# fpga-bank4-outside.net
KiCad netlist of a schematic drawn in Altium Designer
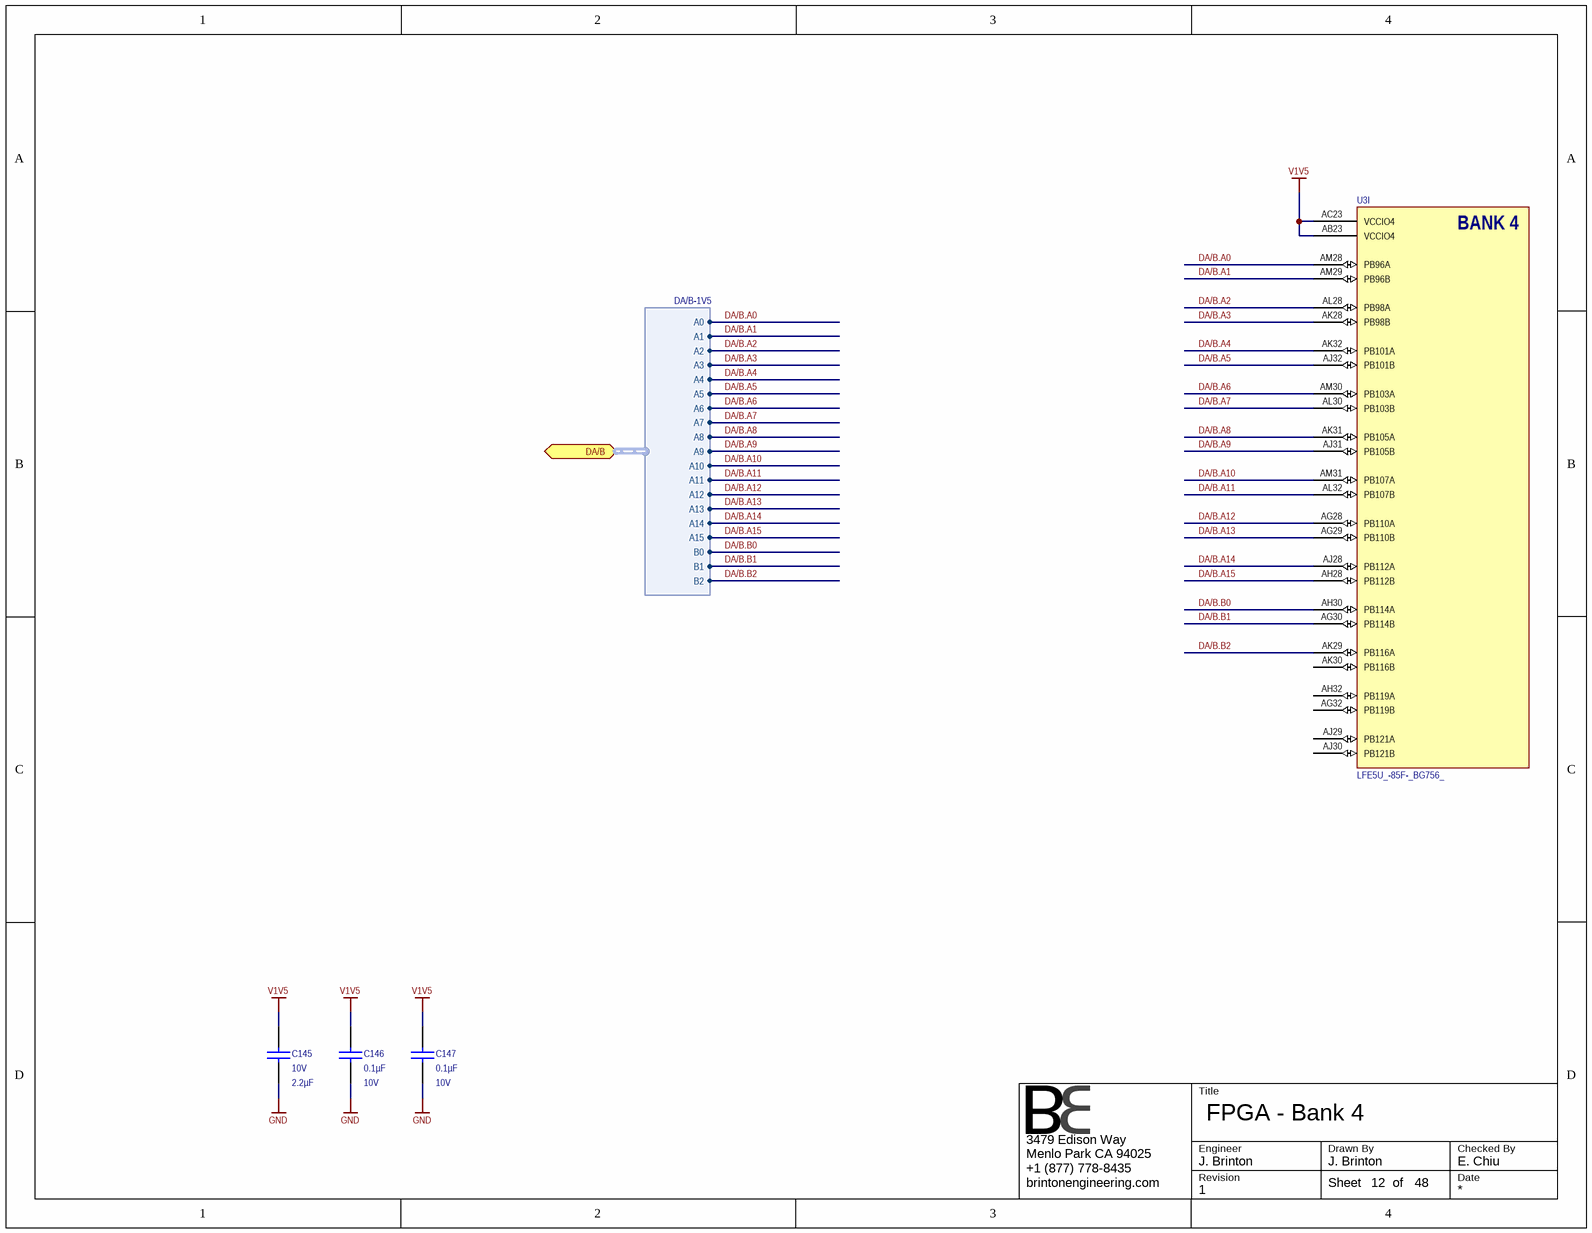
[diagram p0: fpga-bank4-outside.SchDoc]

(export (version "E")
  (design (tool "Eeschema 10.0.6"))
  (components
    (comp (ref "C145")
      (value "GRM188R71A225KE15D")
      (footprint "CAPC1608X90N")
      (description "CAP CER 2.2UF 10V 10% X7R 0603")
      (fields
        (field (name "MANUFACTURER") "Murata Electronics North America")
        (field (name "TOLERANCE") "±10%")
        (field (name "VOLTAGE - RATED") "10V")
        (field (name "CAPACITANCE") "2.2µF")
      )
      (libsource (lib "murata") (part "GRM188R71A225KE15D"))
    )
    (comp (ref "C146")
      (value "GRM155R71A104KA01J")
      (footprint "CAPC1005X56N")
      (description "CAP CER 0.1UF 10V 10% X7R 0402")
      (fields
        (field (name "MANUFACTURER") "Murata Electronics North America")
        (field (name "TOLERANCE") "±10%")
        (field (name "CAPACITANCE") "0.1µF")
        (field (name "VOLTAGE - RATED") "10V")
      )
      (libsource (lib "murata") (part "GRM155R71A104KA01J"))
    )
    (comp (ref "C147")
      (value "GRM155R71A104KA01J")
      (footprint "CAPC1005X56N")
      (description "CAP CER 0.1UF 10V 10% X7R 0402")
      (fields
        (field (name "MANUFACTURER") "Murata Electronics North America")
        (field (name "TOLERANCE") "±10%")
        (field (name "CAPACITANCE") "0.1µF")
        (field (name "VOLTAGE - RATED") "10V")
      )
      (libsource (lib "murata") (part "GRM155R71A104KA01J"))
    )
    (comp (ref "U3")
      (value "LFE5U_-85F-_BG756_")
      (footprint "lattice:caBGA756")
      (description "ECP5 FPGA, 85k LUT, 756-caBGA")
      (fields (field (name "MANUFACTURER") "Lattice Semiconductor"))
      (libsource (lib "lattice") (part "LFE5U_-85F-_BG756_"))
    )
  )
  (nets
    (net (code "2") (name "/DA{slash}B.A0") (class "Default")
      (node (ref "U3") (pin "AM28") (pinfunction "PB96A_AM28") (pintype "bidirectional"))
    )
    (net (code "3") (name "/DA{slash}B.A1") (class "Default")
      (node (ref "U3") (pin "AM29") (pinfunction "PB96B_AM29") (pintype "bidirectional"))
    )
    (net (code "4") (name "/DA{slash}B.A2") (class "Default")
      (node (ref "U3") (pin "AL28") (pinfunction "PB98A_AL28") (pintype "bidirectional"))
    )
    (net (code "5") (name "/DA{slash}B.A3") (class "Default")
      (node (ref "U3") (pin "AK28") (pinfunction "PB98B_AK28") (pintype "bidirectional"))
    )
    (net (code "6") (name "/DA{slash}B.A4") (class "Default")
      (node (ref "U3") (pin "AK32") (pinfunction "PB101A_AK32") (pintype "bidirectional"))
    )
    (net (code "7") (name "/DA{slash}B.A5") (class "Default")
      (node (ref "U3") (pin "AJ32") (pinfunction "PB101B_AJ32") (pintype "bidirectional"))
    )
    (net (code "8") (name "/DA{slash}B.A6") (class "Default")
      (node (ref "U3") (pin "AM30") (pinfunction "PB103A_AM30") (pintype "bidirectional"))
    )
    (net (code "9") (name "/DA{slash}B.A7") (class "Default")
      (node (ref "U3") (pin "AL30") (pinfunction "PB103B_AL30") (pintype "bidirectional"))
    )
    (net (code "10") (name "/DA{slash}B.A8") (class "Default")
      (node (ref "U3") (pin "AK31") (pinfunction "PB105A_AK31") (pintype "bidirectional"))
    )
    (net (code "11") (name "/DA{slash}B.A9") (class "Default")
      (node (ref "U3") (pin "AJ31") (pinfunction "PB105B_AJ31") (pintype "bidirectional"))
    )
    (net (code "12") (name "/DA{slash}B.A10") (class "Default")
      (node (ref "U3") (pin "AM31") (pinfunction "PB107A_AM31") (pintype "bidirectional"))
    )
    (net (code "13") (name "/DA{slash}B.A11") (class "Default")
      (node (ref "U3") (pin "AL32") (pinfunction "PB107B_AL32") (pintype "bidirectional"))
    )
    (net (code "14") (name "/DA{slash}B.A12") (class "Default")
      (node (ref "U3") (pin "AG28") (pinfunction "PB110A_AG28") (pintype "bidirectional"))
    )
    (net (code "15") (name "/DA{slash}B.A13") (class "Default")
      (node (ref "U3") (pin "AG29") (pinfunction "PB110B_AG29") (pintype "bidirectional"))
    )
    (net (code "16") (name "/DA{slash}B.A14") (class "Default")
      (node (ref "U3") (pin "AJ28") (pinfunction "PB112A_AJ28") (pintype "bidirectional"))
    )
    (net (code "17") (name "/DA{slash}B.A15") (class "Default")
      (node (ref "U3") (pin "AH28") (pinfunction "PB112B_AH28") (pintype "bidirectional"))
    )
    (net (code "18") (name "/DA{slash}B.B0") (class "Default")
      (node (ref "U3") (pin "AH30") (pinfunction "PB114A_AH30") (pintype "bidirectional"))
    )
    (net (code "19") (name "/DA{slash}B.B1") (class "Default")
      (node (ref "U3") (pin "AG30") (pinfunction "PB114B_AG30") (pintype "bidirectional"))
    )
    (net (code "20") (name "/DA{slash}B.B2") (class "Default")
      (node (ref "U3") (pin "AK29") (pinfunction "PB116A_AK29") (pintype "bidirectional"))
    )
    (net (code "22") (name "GND") (class "Default")
      (node (ref "C145") (pin "1") (pinfunction "1_1") (pintype "passive"))
      (node (ref "C146") (pin "1") (pinfunction "1_1") (pintype "passive"))
      (node (ref "C147") (pin "1") (pinfunction "1_1") (pintype "passive"))
    )
    (net (code "23") (name "V1V5") (class "Default")
      (node (ref "C145") (pin "2") (pinfunction "2_2") (pintype "passive"))
      (node (ref "C146") (pin "2") (pinfunction "2_2") (pintype "passive"))
      (node (ref "C147") (pin "2") (pinfunction "2_2") (pintype "passive"))
      (node (ref "U3") (pin "AB23") (pinfunction "VCCIO4_AB23") (pintype "power_in"))
      (node (ref "U3") (pin "AC23") (pinfunction "VCCIO4_AC23") (pintype "power_in"))
    )
    (net (code "24") (name "unconnected-(U3I-PB116B-PadAK30)") (class "Default")
      (node (ref "U3") (pin "AK30") (pinfunction "PB116B_AK30") (pintype "bidirectional"))
    )
    (net (code "25") (name "unconnected-(U3I-PB119A-PadAH32)") (class "Default")
      (node (ref "U3") (pin "AH32") (pinfunction "PB119A_AH32") (pintype "bidirectional"))
    )
    (net (code "26") (name "unconnected-(U3I-PB119B-PadAG32)") (class "Default")
      (node (ref "U3") (pin "AG32") (pinfunction "PB119B_AG32") (pintype "bidirectional"))
    )
    (net (code "27") (name "unconnected-(U3I-PB121A-PadAJ29)") (class "Default")
      (node (ref "U3") (pin "AJ29") (pinfunction "PB121A_AJ29") (pintype "bidirectional"))
    )
    (net (code "28") (name "unconnected-(U3I-PB121B-PadAJ30)") (class "Default")
      (node (ref "U3") (pin "AJ30") (pinfunction "PB121B_AJ30") (pintype "bidirectional"))
    )
  )
)
